# cnc_driver.net
KiCad netlist of a schematic drawn in EAGLE
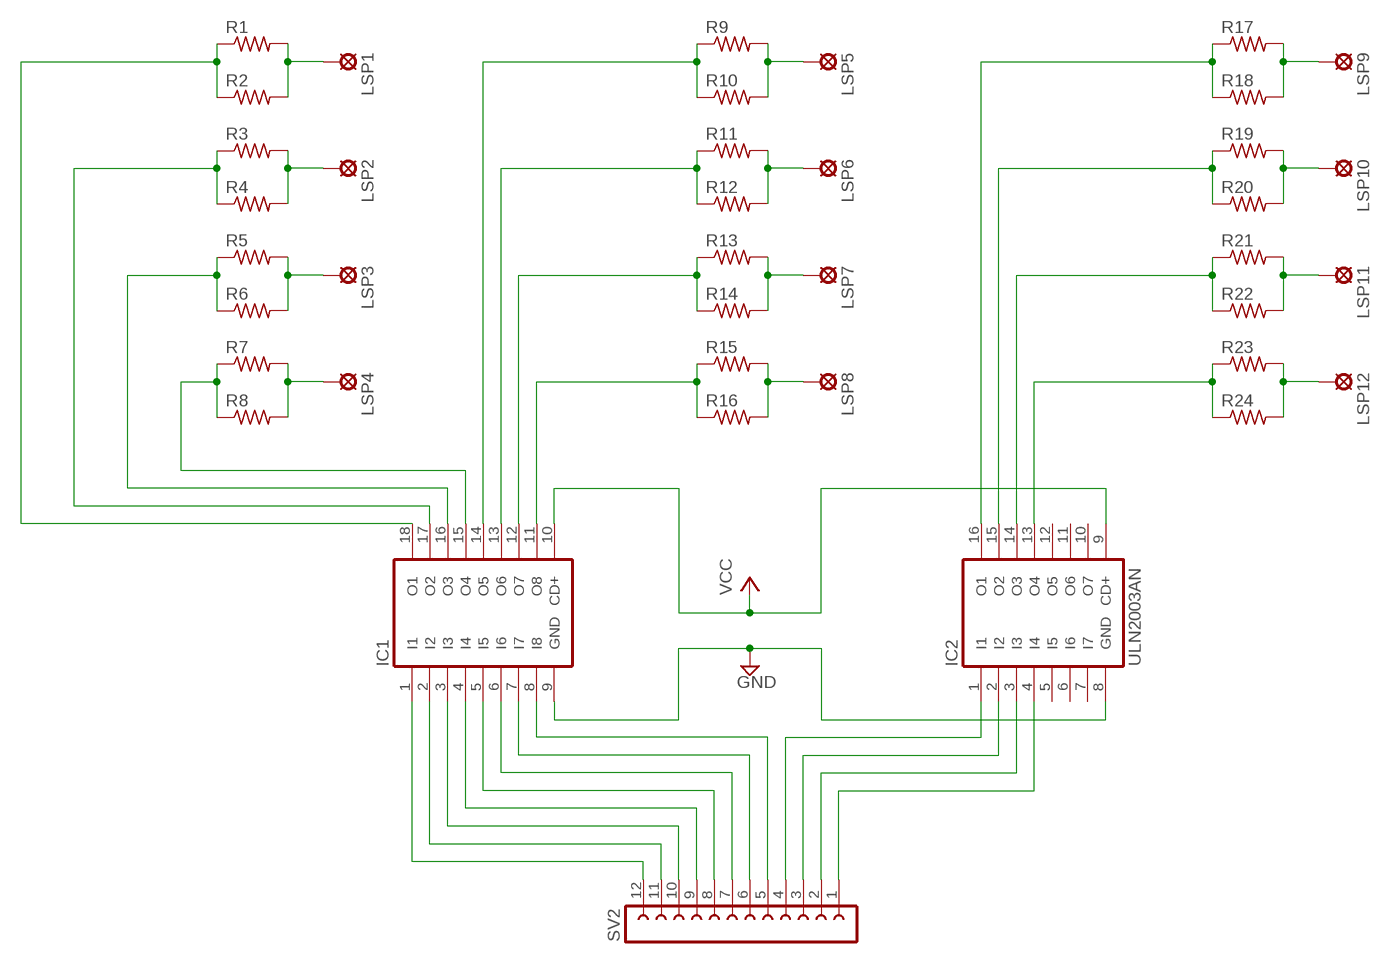
[diagram p0: schematic, sheet 1]

(export (version "E")
  (design (tool "Eeschema 10.0.6"))
  (components
    (comp (ref "IC1")
      (value "ULN2803A")
      (footprint "eagle-import:DIL18")
      (libsource (lib "eagle-import") (part "ULN2803A"))
    )
    (comp (ref "IC2")
      (value "ULN2003AN")
      (footprint "eagle-import:DIL16")
      (libsource (lib "eagle-import") (part "ULN2003AN"))
    )
    (comp (ref "LSP1")
      (value "LSP11")
      (footprint "eagle-import:LSP11")
      (libsource (lib "eagle-import") (part "LSP11"))
    )
    (comp (ref "LSP2")
      (value "LSP11")
      (footprint "eagle-import:LSP11")
      (libsource (lib "eagle-import") (part "LSP11"))
    )
    (comp (ref "LSP3")
      (value "LSP11")
      (footprint "eagle-import:LSP11")
      (libsource (lib "eagle-import") (part "LSP11"))
    )
    (comp (ref "LSP4")
      (value "LSP11")
      (footprint "eagle-import:LSP11")
      (libsource (lib "eagle-import") (part "LSP11"))
    )
    (comp (ref "LSP5")
      (value "LSP11")
      (footprint "eagle-import:LSP11")
      (libsource (lib "eagle-import") (part "LSP11"))
    )
    (comp (ref "LSP6")
      (value "LSP11")
      (footprint "eagle-import:LSP11")
      (libsource (lib "eagle-import") (part "LSP11"))
    )
    (comp (ref "LSP7")
      (value "LSP11")
      (footprint "eagle-import:LSP11")
      (libsource (lib "eagle-import") (part "LSP11"))
    )
    (comp (ref "LSP8")
      (value "LSP11")
      (footprint "eagle-import:LSP11")
      (libsource (lib "eagle-import") (part "LSP11"))
    )
    (comp (ref "LSP9")
      (value "LSP11")
      (footprint "eagle-import:LSP11")
      (libsource (lib "eagle-import") (part "LSP11"))
    )
    (comp (ref "LSP10")
      (value "LSP11")
      (footprint "eagle-import:LSP11")
      (libsource (lib "eagle-import") (part "LSP11"))
    )
    (comp (ref "LSP11")
      (value "LSP11")
      (footprint "eagle-import:LSP11")
      (libsource (lib "eagle-import") (part "LSP11"))
    )
    (comp (ref "LSP12")
      (value "LSP11")
      (footprint "eagle-import:LSP11")
      (libsource (lib "eagle-import") (part "LSP11"))
    )
    (comp (ref "R1")
      (value "R-US_0922V")
      (footprint "eagle-import:0922V")
      (libsource (lib "eagle-import") (part "R-US_0922V"))
    )
    (comp (ref "R2")
      (value "R-US_0922V")
      (footprint "eagle-import:0922V")
      (libsource (lib "eagle-import") (part "R-US_0922V"))
    )
    (comp (ref "R3")
      (value "R-US_0922V")
      (footprint "eagle-import:0922V")
      (libsource (lib "eagle-import") (part "R-US_0922V"))
    )
    (comp (ref "R4")
      (value "R-US_0922V")
      (footprint "eagle-import:0922V")
      (libsource (lib "eagle-import") (part "R-US_0922V"))
    )
    (comp (ref "R5")
      (value "R-US_0922V")
      (footprint "eagle-import:0922V")
      (libsource (lib "eagle-import") (part "R-US_0922V"))
    )
    (comp (ref "R6")
      (value "R-US_0922V")
      (footprint "eagle-import:0922V")
      (libsource (lib "eagle-import") (part "R-US_0922V"))
    )
    (comp (ref "R7")
      (value "R-US_0922V")
      (footprint "eagle-import:0922V")
      (libsource (lib "eagle-import") (part "R-US_0922V"))
    )
    (comp (ref "R8")
      (value "R-US_0922V")
      (footprint "eagle-import:0922V")
      (libsource (lib "eagle-import") (part "R-US_0922V"))
    )
    (comp (ref "R9")
      (value "R-US_0922V")
      (footprint "eagle-import:0922V")
      (libsource (lib "eagle-import") (part "R-US_0922V"))
    )
    (comp (ref "R10")
      (value "R-US_0922V")
      (footprint "eagle-import:0922V")
      (libsource (lib "eagle-import") (part "R-US_0922V"))
    )
    (comp (ref "R11")
      (value "R-US_0922V")
      (footprint "eagle-import:0922V")
      (libsource (lib "eagle-import") (part "R-US_0922V"))
    )
    (comp (ref "R12")
      (value "R-US_0922V")
      (footprint "eagle-import:0922V")
      (libsource (lib "eagle-import") (part "R-US_0922V"))
    )
    (comp (ref "R13")
      (value "R-US_0922V")
      (footprint "eagle-import:0922V")
      (libsource (lib "eagle-import") (part "R-US_0922V"))
    )
    (comp (ref "R14")
      (value "R-US_0922V")
      (footprint "eagle-import:0922V")
      (libsource (lib "eagle-import") (part "R-US_0922V"))
    )
    (comp (ref "R15")
      (value "R-US_0922V")
      (footprint "eagle-import:0922V")
      (libsource (lib "eagle-import") (part "R-US_0922V"))
    )
    (comp (ref "R16")
      (value "R-US_0922V")
      (footprint "eagle-import:0922V")
      (libsource (lib "eagle-import") (part "R-US_0922V"))
    )
    (comp (ref "R17")
      (value "R-US_0922V")
      (footprint "eagle-import:0922V")
      (libsource (lib "eagle-import") (part "R-US_0922V"))
    )
    (comp (ref "R18")
      (value "R-US_0922V")
      (footprint "eagle-import:0922V")
      (libsource (lib "eagle-import") (part "R-US_0922V"))
    )
    (comp (ref "R19")
      (value "R-US_0922V")
      (footprint "eagle-import:0922V")
      (libsource (lib "eagle-import") (part "R-US_0922V"))
    )
    (comp (ref "R20")
      (value "R-US_0922V")
      (footprint "eagle-import:0922V")
      (libsource (lib "eagle-import") (part "R-US_0922V"))
    )
    (comp (ref "R21")
      (value "R-US_0922V")
      (footprint "eagle-import:0922V")
      (libsource (lib "eagle-import") (part "R-US_0922V"))
    )
    (comp (ref "R22")
      (value "R-US_0922V")
      (footprint "eagle-import:0922V")
      (libsource (lib "eagle-import") (part "R-US_0922V"))
    )
    (comp (ref "R23")
      (value "R-US_0922V")
      (footprint "eagle-import:0922V")
      (libsource (lib "eagle-import") (part "R-US_0922V"))
    )
    (comp (ref "R24")
      (value "R-US_0922V")
      (footprint "eagle-import:0922V")
      (libsource (lib "eagle-import") (part "R-US_0922V"))
    )
    (comp (ref "SV2")
      (value "FE12-1")
      (footprint "eagle-import:FE12")
      (libsource (lib "eagle-import") (part "FE12-1"))
    )
  )
  (nets
    (net (code "1") (name "GND") (class "Default")
      (node (ref "IC1") (pin "9") (pinfunction "GND_9") (pintype "power_in"))
      (node (ref "IC2") (pin "8") (pinfunction "GND_8") (pintype "power_in"))
    )
    (net (code "2") (name "Net-(IC1-I1)") (class "Default")
      (node (ref "IC1") (pin "1") (pinfunction "I1_1") (pintype "input"))
      (node (ref "SV2") (pin "12") (pinfunction "12_12") (pintype "passive"))
    )
    (net (code "3") (name "Net-(IC1-I2)") (class "Default")
      (node (ref "IC1") (pin "2") (pinfunction "I2_2") (pintype "input"))
      (node (ref "SV2") (pin "11") (pinfunction "11_11") (pintype "passive"))
    )
    (net (code "4") (name "Net-(IC1-I3)") (class "Default")
      (node (ref "IC1") (pin "3") (pinfunction "I3_3") (pintype "input"))
      (node (ref "SV2") (pin "10") (pinfunction "10_10") (pintype "passive"))
    )
    (net (code "5") (name "Net-(IC1-I4)") (class "Default")
      (node (ref "IC1") (pin "4") (pinfunction "I4_4") (pintype "input"))
      (node (ref "SV2") (pin "9") (pinfunction "9_9") (pintype "passive"))
    )
    (net (code "6") (name "Net-(IC1-I5)") (class "Default")
      (node (ref "IC1") (pin "5") (pinfunction "I5_5") (pintype "input"))
      (node (ref "SV2") (pin "8") (pinfunction "8_8") (pintype "passive"))
    )
    (net (code "7") (name "Net-(IC1-I6)") (class "Default")
      (node (ref "IC1") (pin "6") (pinfunction "I6_6") (pintype "input"))
      (node (ref "SV2") (pin "7") (pinfunction "7_7") (pintype "passive"))
    )
    (net (code "8") (name "Net-(IC1-I7)") (class "Default")
      (node (ref "IC1") (pin "7") (pinfunction "I7_7") (pintype "input"))
      (node (ref "SV2") (pin "6") (pinfunction "6_6") (pintype "passive"))
    )
    (net (code "9") (name "Net-(IC1-I8)") (class "Default")
      (node (ref "IC1") (pin "8") (pinfunction "I8_8") (pintype "input"))
      (node (ref "SV2") (pin "5") (pinfunction "5_5") (pintype "passive"))
    )
    (net (code "10") (name "Net-(IC1-O1)") (class "Default")
      (node (ref "IC1") (pin "18") (pinfunction "O1_18") (pintype "open_collector"))
      (node (ref "R1") (pin "1") (pinfunction "1_1") (pintype "passive"))
      (node (ref "R2") (pin "1") (pinfunction "1_1") (pintype "passive"))
    )
    (net (code "11") (name "Net-(IC1-O2)") (class "Default")
      (node (ref "IC1") (pin "17") (pinfunction "O2_17") (pintype "open_collector"))
      (node (ref "R3") (pin "1") (pinfunction "1_1") (pintype "passive"))
      (node (ref "R4") (pin "1") (pinfunction "1_1") (pintype "passive"))
    )
    (net (code "12") (name "Net-(IC1-O3)") (class "Default")
      (node (ref "IC1") (pin "16") (pinfunction "O3_16") (pintype "open_collector"))
      (node (ref "R5") (pin "1") (pinfunction "1_1") (pintype "passive"))
      (node (ref "R6") (pin "1") (pinfunction "1_1") (pintype "passive"))
    )
    (net (code "13") (name "Net-(IC1-O4)") (class "Default")
      (node (ref "IC1") (pin "15") (pinfunction "O4_15") (pintype "open_collector"))
      (node (ref "R7") (pin "1") (pinfunction "1_1") (pintype "passive"))
      (node (ref "R8") (pin "1") (pinfunction "1_1") (pintype "passive"))
    )
    (net (code "14") (name "Net-(IC1-O5)") (class "Default")
      (node (ref "IC1") (pin "14") (pinfunction "O5_14") (pintype "open_collector"))
      (node (ref "R10") (pin "1") (pinfunction "1_1") (pintype "passive"))
      (node (ref "R9") (pin "1") (pinfunction "1_1") (pintype "passive"))
    )
    (net (code "15") (name "Net-(IC1-O6)") (class "Default")
      (node (ref "IC1") (pin "13") (pinfunction "O6_13") (pintype "open_collector"))
      (node (ref "R11") (pin "1") (pinfunction "1_1") (pintype "passive"))
      (node (ref "R12") (pin "1") (pinfunction "1_1") (pintype "passive"))
    )
    (net (code "16") (name "Net-(IC1-O7)") (class "Default")
      (node (ref "IC1") (pin "12") (pinfunction "O7_12") (pintype "open_collector"))
      (node (ref "R13") (pin "1") (pinfunction "1_1") (pintype "passive"))
      (node (ref "R14") (pin "1") (pinfunction "1_1") (pintype "passive"))
    )
    (net (code "17") (name "Net-(IC1-O8)") (class "Default")
      (node (ref "IC1") (pin "11") (pinfunction "O8_11") (pintype "open_collector"))
      (node (ref "R15") (pin "1") (pinfunction "1_1") (pintype "passive"))
      (node (ref "R16") (pin "1") (pinfunction "1_1") (pintype "passive"))
    )
    (net (code "18") (name "Net-(IC2-I1)") (class "Default")
      (node (ref "IC2") (pin "1") (pinfunction "I1_1") (pintype "input"))
      (node (ref "SV2") (pin "4") (pinfunction "4_4") (pintype "passive"))
    )
    (net (code "19") (name "Net-(IC2-I2)") (class "Default")
      (node (ref "IC2") (pin "2") (pinfunction "I2_2") (pintype "input"))
      (node (ref "SV2") (pin "3") (pinfunction "3_3") (pintype "passive"))
    )
    (net (code "20") (name "Net-(IC2-I3)") (class "Default")
      (node (ref "IC2") (pin "3") (pinfunction "I3_3") (pintype "input"))
      (node (ref "SV2") (pin "2") (pinfunction "2_2") (pintype "passive"))
    )
    (net (code "21") (name "Net-(IC2-I4)") (class "Default")
      (node (ref "IC2") (pin "4") (pinfunction "I4_4") (pintype "input"))
      (node (ref "SV2") (pin "1") (pinfunction "1_1") (pintype "passive"))
    )
    (net (code "22") (name "Net-(IC2-O1)") (class "Default")
      (node (ref "IC2") (pin "16") (pinfunction "O1_16") (pintype "open_collector"))
      (node (ref "R17") (pin "1") (pinfunction "1_1") (pintype "passive"))
      (node (ref "R18") (pin "1") (pinfunction "1_1") (pintype "passive"))
    )
    (net (code "23") (name "Net-(IC2-O2)") (class "Default")
      (node (ref "IC2") (pin "15") (pinfunction "O2_15") (pintype "open_collector"))
      (node (ref "R19") (pin "1") (pinfunction "1_1") (pintype "passive"))
      (node (ref "R20") (pin "1") (pinfunction "1_1") (pintype "passive"))
    )
    (net (code "24") (name "Net-(IC2-O3)") (class "Default")
      (node (ref "IC2") (pin "14") (pinfunction "O3_14") (pintype "open_collector"))
      (node (ref "R21") (pin "1") (pinfunction "1_1") (pintype "passive"))
      (node (ref "R22") (pin "1") (pinfunction "1_1") (pintype "passive"))
    )
    (net (code "25") (name "Net-(IC2-O4)") (class "Default")
      (node (ref "IC2") (pin "13") (pinfunction "O4_13") (pintype "open_collector"))
      (node (ref "R23") (pin "1") (pinfunction "1_1") (pintype "passive"))
      (node (ref "R24") (pin "1") (pinfunction "1_1") (pintype "passive"))
    )
    (net (code "26") (name "Net-(LSP1-PadMP)") (class "Default")
      (node (ref "LSP1") (pin "MP") (pinfunction "MP_MP") (pintype "passive"))
      (node (ref "R1") (pin "2") (pinfunction "2_2") (pintype "passive"))
      (node (ref "R2") (pin "2") (pinfunction "2_2") (pintype "passive"))
    )
    (net (code "27") (name "Net-(LSP2-PadMP)") (class "Default")
      (node (ref "LSP2") (pin "MP") (pinfunction "MP_MP") (pintype "passive"))
      (node (ref "R3") (pin "2") (pinfunction "2_2") (pintype "passive"))
      (node (ref "R4") (pin "2") (pinfunction "2_2") (pintype "passive"))
    )
    (net (code "28") (name "Net-(LSP3-PadMP)") (class "Default")
      (node (ref "LSP3") (pin "MP") (pinfunction "MP_MP") (pintype "passive"))
      (node (ref "R5") (pin "2") (pinfunction "2_2") (pintype "passive"))
      (node (ref "R6") (pin "2") (pinfunction "2_2") (pintype "passive"))
    )
    (net (code "29") (name "Net-(LSP4-PadMP)") (class "Default")
      (node (ref "LSP4") (pin "MP") (pinfunction "MP_MP") (pintype "passive"))
      (node (ref "R7") (pin "2") (pinfunction "2_2") (pintype "passive"))
      (node (ref "R8") (pin "2") (pinfunction "2_2") (pintype "passive"))
    )
    (net (code "30") (name "Net-(LSP5-PadMP)") (class "Default")
      (node (ref "LSP5") (pin "MP") (pinfunction "MP_MP") (pintype "passive"))
      (node (ref "R10") (pin "2") (pinfunction "2_2") (pintype "passive"))
      (node (ref "R9") (pin "2") (pinfunction "2_2") (pintype "passive"))
    )
    (net (code "31") (name "Net-(LSP6-PadMP)") (class "Default")
      (node (ref "LSP6") (pin "MP") (pinfunction "MP_MP") (pintype "passive"))
      (node (ref "R11") (pin "2") (pinfunction "2_2") (pintype "passive"))
      (node (ref "R12") (pin "2") (pinfunction "2_2") (pintype "passive"))
    )
    (net (code "32") (name "Net-(LSP7-PadMP)") (class "Default")
      (node (ref "LSP7") (pin "MP") (pinfunction "MP_MP") (pintype "passive"))
      (node (ref "R13") (pin "2") (pinfunction "2_2") (pintype "passive"))
      (node (ref "R14") (pin "2") (pinfunction "2_2") (pintype "passive"))
    )
    (net (code "33") (name "Net-(LSP8-PadMP)") (class "Default")
      (node (ref "LSP8") (pin "MP") (pinfunction "MP_MP") (pintype "passive"))
      (node (ref "R15") (pin "2") (pinfunction "2_2") (pintype "passive"))
      (node (ref "R16") (pin "2") (pinfunction "2_2") (pintype "passive"))
    )
    (net (code "34") (name "Net-(LSP9-PadMP)") (class "Default")
      (node (ref "LSP9") (pin "MP") (pinfunction "MP_MP") (pintype "passive"))
      (node (ref "R17") (pin "2") (pinfunction "2_2") (pintype "passive"))
      (node (ref "R18") (pin "2") (pinfunction "2_2") (pintype "passive"))
    )
    (net (code "35") (name "Net-(LSP10-PadMP)") (class "Default")
      (node (ref "LSP10") (pin "MP") (pinfunction "MP_MP") (pintype "passive"))
      (node (ref "R19") (pin "2") (pinfunction "2_2") (pintype "passive"))
      (node (ref "R20") (pin "2") (pinfunction "2_2") (pintype "passive"))
    )
    (net (code "36") (name "Net-(LSP11-PadMP)") (class "Default")
      (node (ref "LSP11") (pin "MP") (pinfunction "MP_MP") (pintype "passive"))
      (node (ref "R21") (pin "2") (pinfunction "2_2") (pintype "passive"))
      (node (ref "R22") (pin "2") (pinfunction "2_2") (pintype "passive"))
    )
    (net (code "37") (name "Net-(LSP12-PadMP)") (class "Default")
      (node (ref "LSP12") (pin "MP") (pinfunction "MP_MP") (pintype "passive"))
      (node (ref "R23") (pin "2") (pinfunction "2_2") (pintype "passive"))
      (node (ref "R24") (pin "2") (pinfunction "2_2") (pintype "passive"))
    )
    (net (code "38") (name "VCC") (class "Default")
      (node (ref "IC1") (pin "10") (pinfunction "CD+_10") (pintype "passive"))
      (node (ref "IC2") (pin "9") (pinfunction "CD+_9") (pintype "passive"))
    )
    (net (code "39") (name "unconnected-(IC2-I5-Pad5)") (class "Default")
      (node (ref "IC2") (pin "5") (pinfunction "I5_5") (pintype "input"))
    )
    (net (code "40") (name "unconnected-(IC2-I6-Pad6)") (class "Default")
      (node (ref "IC2") (pin "6") (pinfunction "I6_6") (pintype "input"))
    )
    (net (code "41") (name "unconnected-(IC2-I7-Pad7)") (class "Default")
      (node (ref "IC2") (pin "7") (pinfunction "I7_7") (pintype "input"))
    )
    (net (code "42") (name "unconnected-(IC2-O5-Pad12)") (class "Default")
      (node (ref "IC2") (pin "12") (pinfunction "O5_12") (pintype "open_collector"))
    )
    (net (code "43") (name "unconnected-(IC2-O6-Pad11)") (class "Default")
      (node (ref "IC2") (pin "11") (pinfunction "O6_11") (pintype "open_collector"))
    )
    (net (code "44") (name "unconnected-(IC2-O7-Pad10)") (class "Default")
      (node (ref "IC2") (pin "10") (pinfunction "O7_10") (pintype "open_collector"))
    )
  )
)
